# indicators.net
KiCad netlist of a schematic drawn in Altium Designer
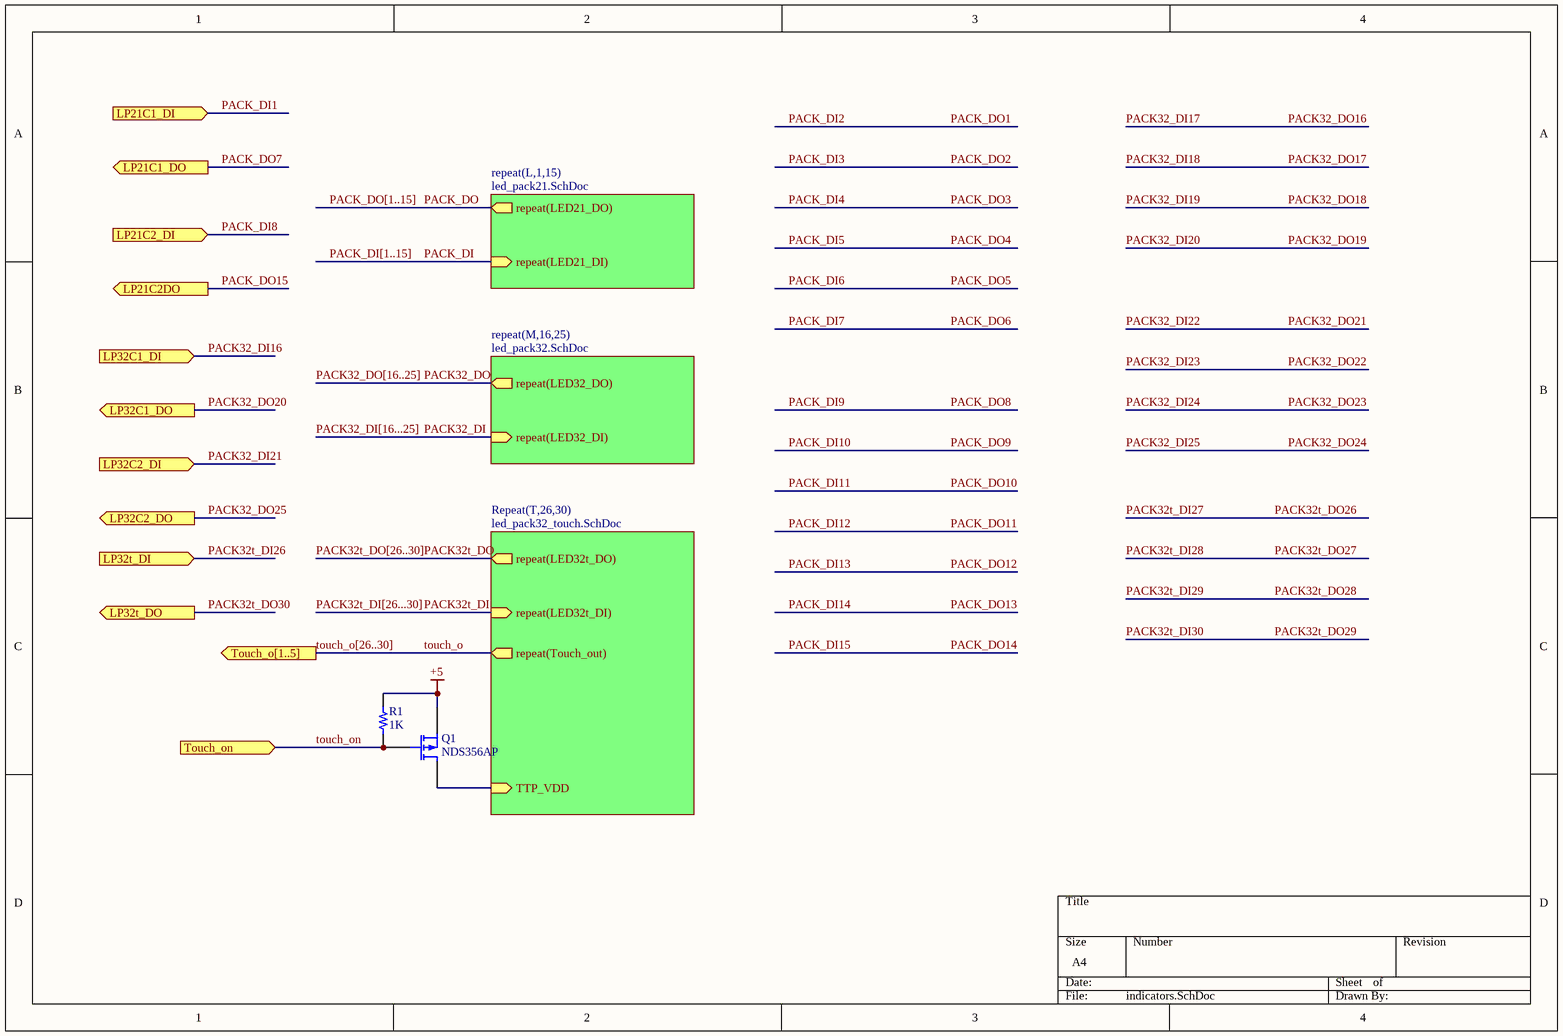
[diagram p0: indicators.SchDoc]

(export (version "E")
  (design (tool "Eeschema 10.0.6"))
  (components
    (comp (ref "Q1")
      (value "NDS356AP")
      (footprint "soT95p280x130-3n")
      (description "P-Channel MOSFET SOT23")
      (fields (field (name "PUBLISHER") "Altium Limited"))
      (libsource (lib "Miscellaneous Devices") (part "MOSFET-P"))
    )
    (comp (ref "R1")
      (value "1K")
      (footprint "0603R")
      (description "RES SMD 0603")
      (fields (field (name "PART NUMBER") "RCS0805100KFKEA"))
      (libsource (lib "lamp control-ver2") (part "Resistor"))
    )
  )
  (nets
    (net (code "8") (name "+5") (class "Default")
      (node (ref "Q1") (pin "3") (pinfunction "S_3") (pintype "passive"))
      (node (ref "R1") (pin "1") (pinfunction "1_1") (pintype "passive"))
    )
    (net (code "54") (name "/TTP_VDD") (class "Default")
      (node (ref "Q1") (pin "1") (pinfunction "D_1") (pintype "passive"))
    )
    (net (code "57") (name "/touch_on") (class "Default")
      (node (ref "Q1") (pin "2") (pinfunction "G_2") (pintype "passive"))
      (node (ref "R1") (pin "2") (pinfunction "2_2") (pintype "passive"))
    )
  )
)
